# C_3_1.net
KiCad netlist of a schematic drawn in EasyEDA Pro
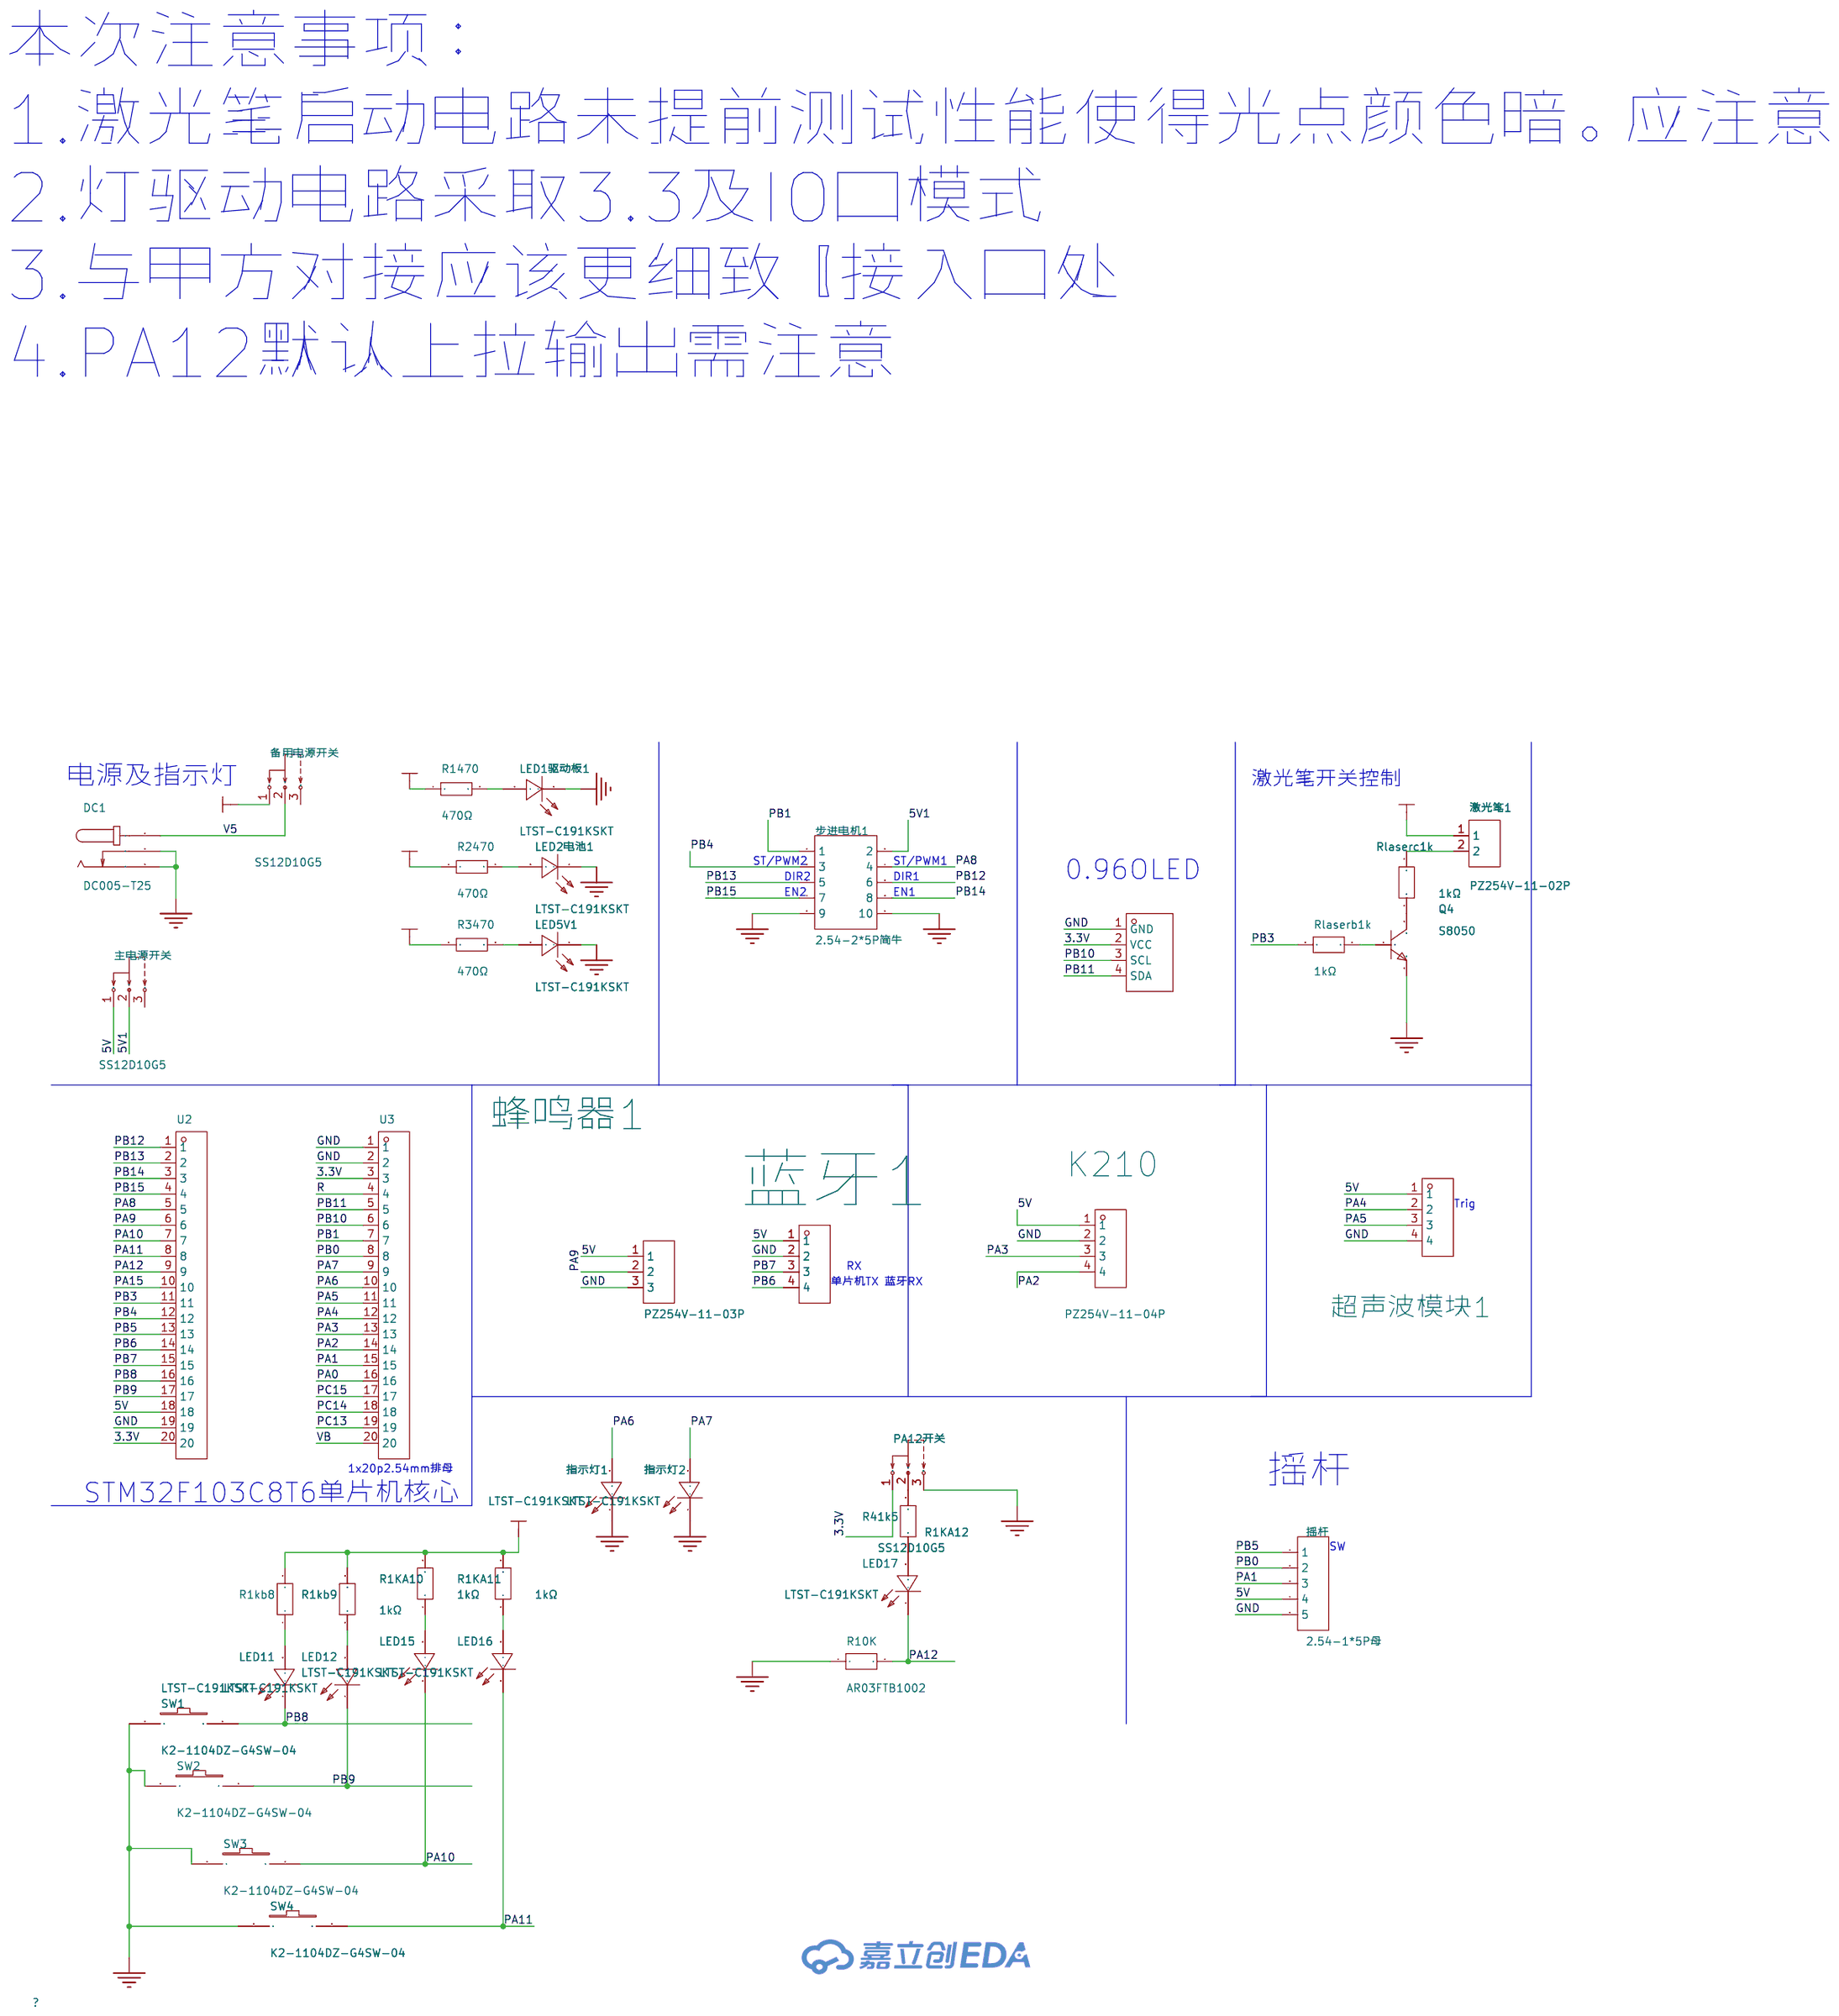
[diagram p0: schematic sheet]

(export (version "E")
  (design (tool "Eeschema 10.0.6"))
  (components
    (comp (ref "DC1")
      (value "DC005-T25")
      (footprint "easyedapro:DC-IN-TH_DC-005-20A-1")
      (description "触点内径:2.5mm;触点外径:6.3mm;额定电流:-;额定电压:-;")
      (fields (field (name "Manufacturer") "SOFNG(硕方)"))
      (libsource (lib "easyedapro") (part "DC005-2.5MM"))
    )
    (comp (ref "K210")
      (value "PZ254V-11-04P")
      (footprint "easyedapro:HDR-TH_4P-P2.54-V-M")
      (fields (field (name "Manufacturer") "XFCN(兴飞)"))
      (libsource (lib "easyedapro") (part "PZ254V-11-04P_C2691448"))
    )
    (comp (ref "LED1驱动板1")
      (value "LTST-C191KSKT")
      (footprint "easyedapro:LED0603-RD-YELLOW")
      (fields (field (name "Manufacturer") "LITEON(光宝)"))
      (libsource (lib "easyedapro") (part "LTST-C191KSKT"))
    )
    (comp (ref "LED2电池1")
      (value "LTST-C191KSKT")
      (footprint "easyedapro:LED0603-RD-YELLOW")
      (fields (field (name "Manufacturer") "LITEON(光宝)"))
      (libsource (lib "easyedapro") (part "LTST-C191KSKT"))
    )
    (comp (ref "LED5V1")
      (value "LTST-C191KSKT")
      (footprint "easyedapro:LED0603-RD-YELLOW")
      (fields (field (name "Manufacturer") "LITEON(光宝)"))
      (libsource (lib "easyedapro") (part "LTST-C191KSKT"))
    )
    (comp (ref "LED11")
      (value "LTST-C191KSKT")
      (footprint "easyedapro:LED0603-RD-YELLOW")
      (fields (field (name "Manufacturer") "LITEON(光宝)"))
      (libsource (lib "easyedapro") (part "LTST-C191KSKT"))
    )
    (comp (ref "LED12")
      (value "LTST-C191KSKT")
      (footprint "easyedapro:LED0603-RD-YELLOW")
      (fields (field (name "Manufacturer") "LITEON(光宝)"))
      (libsource (lib "easyedapro") (part "LTST-C191KSKT"))
    )
    (comp (ref "LED15")
      (value "LTST-C191KSKT")
      (footprint "easyedapro:LED0603-RD-YELLOW")
      (fields (field (name "Manufacturer") "LITEON(光宝)"))
      (libsource (lib "easyedapro") (part "LTST-C191KSKT"))
    )
    (comp (ref "LED16")
      (value "LTST-C191KSKT")
      (footprint "easyedapro:LED0603-RD-YELLOW")
      (fields (field (name "Manufacturer") "LITEON(光宝)"))
      (libsource (lib "easyedapro") (part "LTST-C191KSKT"))
    )
    (comp (ref "LED17")
      (value "LTST-C191KSKT")
      (footprint "easyedapro:LED0603-RD-YELLOW")
      (fields (field (name "Manufacturer") "LITEON(光宝)"))
      (libsource (lib "easyedapro") (part "LTST-C191KSKT"))
    )
    (comp (ref "OLED1")
      (value "HS96L03W2C03")
      (footprint "easyedapro:OLED-TH_L27.8-W27.2-P2.54_C9900033791")
      (description "主控芯片:SSD1315;接口类型:I2C;尺寸(inch):0.96;像素分辨率:128x64;")
      (fields (field (name "Manufacturer") "HS(汉昇)"))
      (libsource (lib "easyedapro") (part "HS96L03W2C03"))
    )
    (comp (ref "PA12开关")
      (value "SS12D10G5")
      (footprint "easyedapro:SW-TH_SHOU-HAN_SS12D10G4")
      (description "电路结构:单刀双掷;安装方式:直插;额定电流(DC):2A;额定电压(DC):125V;机械寿命:3千次;")
      (fields (field (name "Manufacturer") "SHOU HAN(首韩)"))
      (libsource (lib "easyedapro") (part "SS12D10G5"))
    )
    (comp (ref "Q4")
      (value "S8050")
      (footprint "easyedapro:SOT-23-3_L2.9-W1.6-P1.90-LS2.8-BR")
      (description "晶体管类型:NPN;集电极电流(Ic):500mA;集射极击穿电压(Vceo):25V;功率(Pd):300mW;")
      (fields (field (name "Manufacturer") "Hottech(合科泰)"))
      (libsource (lib "easyedapro") (part "S8050_C181158"))
    )
    (comp (ref "R1KA10")
      (value "1kΩ")
      (footprint "easyedapro:R0603")
      (description "电阻类型:厚膜电阻;阻值:1kΩ;精度:±1%;功率:100mW;最大工作电压:75V;")
      (fields (field (name "Manufacturer Part") "FCR0603F1K") (field (name "Manufacturer") "VO(翔胜)"))
      (libsource (lib "easyedapro") (part "FCR0603F1K"))
    )
    (comp (ref "R1KA11")
      (value "1kΩ")
      (footprint "easyedapro:R0603")
      (description "电阻类型:厚膜电阻;阻值:1kΩ;精度:±1%;功率:100mW;最大工作电压:75V;")
      (fields (field (name "Manufacturer Part") "FCR0603F1K") (field (name "Manufacturer") "VO(翔胜)"))
      (libsource (lib "easyedapro") (part "FCR0603F1K"))
    )
    (comp (ref "R1kb8")
      (value "1kΩ")
      (footprint "easyedapro:R0603")
      (description "电阻类型:厚膜电阻;阻值:1kΩ;精度:±1%;功率:100mW;最大工作电压:75V;")
      (fields (field (name "Manufacturer Part") "FCR0603F1K") (field (name "Manufacturer") "VO(翔胜)"))
      (libsource (lib "easyedapro") (part "FCR0603F1K"))
    )
    (comp (ref "R1kb9")
      (value "1kΩ")
      (footprint "easyedapro:R0603")
      (description "电阻类型:厚膜电阻;阻值:1kΩ;精度:±1%;功率:100mW;最大工作电压:75V;")
      (fields (field (name "Manufacturer Part") "FCR0603F1K") (field (name "Manufacturer") "VO(翔胜)"))
      (libsource (lib "easyedapro") (part "FCR0603F1K"))
    )
    (comp (ref "R10K")
      (value "AR03FTB1002")
      (footprint "easyedapro:R0603")
      (fields (field (name "Manufacturer") "Viking(光颉)"))
      (libsource (lib "easyedapro") (part "AR03FTB1002"))
    )
    (comp (ref "R41k5")
      (value "1kΩ")
      (footprint "easyedapro:R0603")
      (description "电阻类型:厚膜电阻;阻值:1kΩ;精度:±1%;功率:100mW;最大工作电压:75V;")
      (fields (field (name "Manufacturer Part") "FCR0603F1K") (field (name "Manufacturer") "VO(翔胜)"))
      (libsource (lib "easyedapro") (part "FCR0603F1K"))
    )
    (comp (ref "R1470")
      (value "470Ω")
      (footprint "easyedapro:R0603")
      (description "电阻类型:厚膜电阻;阻值:470Ω;精度:±1%;功率:100mW;最大工作电压:75V;温度系数:±100ppm/°C;")
      (fields
        (field (name "Manufacturer Part") "0603WAF4700T5E")
        (field (name "Manufacturer") "UNI-ROYAL(厚声)")
      )
      (libsource (lib "easyedapro") (part "0603WAF4700T5E"))
    )
    (comp (ref "R2470")
      (value "470Ω")
      (footprint "easyedapro:R0603")
      (description "电阻类型:厚膜电阻;阻值:470Ω;精度:±1%;功率:100mW;最大工作电压:75V;温度系数:±100ppm/°C;")
      (fields
        (field (name "Manufacturer Part") "0603WAF4700T5E")
        (field (name "Manufacturer") "UNI-ROYAL(厚声)")
      )
      (libsource (lib "easyedapro") (part "0603WAF4700T5E"))
    )
    (comp (ref "R3470")
      (value "470Ω")
      (footprint "easyedapro:R0603")
      (description "电阻类型:厚膜电阻;阻值:470Ω;精度:±1%;功率:100mW;最大工作电压:75V;温度系数:±100ppm/°C;")
      (fields
        (field (name "Manufacturer Part") "0603WAF4700T5E")
        (field (name "Manufacturer") "UNI-ROYAL(厚声)")
      )
      (libsource (lib "easyedapro") (part "0603WAF4700T5E"))
    )
    (comp (ref "Rlaserb1k")
      (value "1kΩ")
      (footprint "easyedapro:R0603")
      (description "电阻类型:厚膜电阻;阻值:1kΩ;精度:±1%;功率:100mW;最大工作电压:75V;")
      (fields (field (name "Manufacturer Part") "FCR0603F1K") (field (name "Manufacturer") "VO(翔胜)"))
      (libsource (lib "easyedapro") (part "FCR0603F1K"))
    )
    (comp (ref "Rlaserc1k")
      (value "1kΩ")
      (footprint "easyedapro:R0603")
      (description "电阻类型:厚膜电阻;阻值:1kΩ;精度:±1%;功率:100mW;最大工作电压:75V;")
      (fields (field (name "Manufacturer Part") "FCR0603F1K") (field (name "Manufacturer") "VO(翔胜)"))
      (libsource (lib "easyedapro") (part "FCR0603F1K"))
    )
    (comp (ref "SW1")
      (value "K2-1104DZ-G4SW-04")
      (footprint "easyedapro:KEY-TH_2P-L6.0-W6.0-P5.00")
      (description "作用力:250gf;安装方式:直插;开关长度:6mm;开关宽度:6mm;开关高度:7mm;触点电流:50mA;额定电压(DC):12V;绝缘电阻:100MΩ;机械寿命:10万次;")
      (fields (field (name "Manufacturer") "韩国韩荣"))
      (libsource (lib "easyedapro") (part "K2-1104DZ-G4SW-04"))
    )
    (comp (ref "SW2")
      (value "K2-1104DZ-G4SW-04")
      (footprint "easyedapro:KEY-TH_2P-L6.0-W6.0-P5.00")
      (description "作用力:250gf;安装方式:直插;开关长度:6mm;开关宽度:6mm;开关高度:7mm;触点电流:50mA;额定电压(DC):12V;绝缘电阻:100MΩ;机械寿命:10万次;")
      (fields (field (name "Manufacturer") "韩国韩荣"))
      (libsource (lib "easyedapro") (part "K2-1104DZ-G4SW-04"))
    )
    (comp (ref "SW3")
      (value "K2-1104DZ-G4SW-04")
      (footprint "easyedapro:KEY-TH_2P-L6.0-W6.0-P5.00")
      (description "作用力:250gf;安装方式:直插;开关长度:6mm;开关宽度:6mm;开关高度:7mm;触点电流:50mA;额定电压(DC):12V;绝缘电阻:100MΩ;机械寿命:10万次;")
      (fields (field (name "Manufacturer") "韩国韩荣"))
      (libsource (lib "easyedapro") (part "K2-1104DZ-G4SW-04"))
    )
    (comp (ref "SW4")
      (value "K2-1104DZ-G4SW-04")
      (footprint "easyedapro:KEY-TH_2P-L6.0-W6.0-P5.00")
      (description "作用力:250gf;安装方式:直插;开关长度:6mm;开关宽度:6mm;开关高度:7mm;触点电流:50mA;额定电压(DC):12V;绝缘电阻:100MΩ;机械寿命:10万次;")
      (fields (field (name "Manufacturer") "韩国韩荣"))
      (libsource (lib "easyedapro") (part "K2-1104DZ-G4SW-04"))
    )
    (comp (ref "U2")
      (value "KH-2FH-1X20P-H4.3")
      (footprint "easyedapro:HDR-TH_20P-P2.00-V-F-A")
      (fields (field (name "Manufacturer") "kinghelm(金航标)"))
      (libsource (lib "easyedapro") (part "KH-2FH-1X20P-H4.3"))
    )
    (comp (ref "U3")
      (value "KH-2FH-1X20P-H4.3")
      (footprint "easyedapro:HDR-TH_20P-P2.00-V-F-A")
      (fields (field (name "Manufacturer") "kinghelm(金航标)"))
      (libsource (lib "easyedapro") (part "KH-2FH-1X20P-H4.3"))
    )
    (comp (ref "主电源开关")
      (value "SS12D10G5")
      (footprint "easyedapro:SW-TH_SHOU-HAN_SS12D10G4")
      (description "电路结构:单刀双掷;安装方式:直插;额定电流(DC):2A;额定电压(DC):125V;机械寿命:3千次;")
      (fields (field (name "Manufacturer") "SHOU HAN(首韩)"))
      (libsource (lib "easyedapro") (part "SS12D10G5"))
    )
    (comp (ref "备用电源开关")
      (value "SS12D10G5")
      (footprint "easyedapro:SW-TH_SHOU-HAN_SS12D10G4")
      (description "电路结构:单刀双掷;安装方式:直插;额定电流(DC):2A;额定电压(DC):125V;机械寿命:3千次;")
      (fields (field (name "Manufacturer") "SHOU HAN(首韩)"))
      (libsource (lib "easyedapro") (part "SS12D10G5"))
    )
    (comp (ref "指示灯1")
      (value "LTST-C191KSKT")
      (footprint "easyedapro:LED0603-RD-YELLOW")
      (fields (field (name "Manufacturer") "LITEON(光宝)"))
      (libsource (lib "easyedapro") (part "LTST-C191KSKT"))
    )
    (comp (ref "指示灯2")
      (value "LTST-C191KSKT")
      (footprint "easyedapro:LED0603-RD-YELLOW")
      (fields (field (name "Manufacturer") "LITEON(光宝)"))
      (libsource (lib "easyedapro") (part "LTST-C191KSKT"))
    )
    (comp (ref "摇杆")
      (value "2.54-1*5P母")
      (footprint "easyedapro:HDR-TH_5P-P2.54-V-F")
      (description "插孔结构:1x5P;间距:2.54mm;行距:-;安装类型:直插;排数:单排;总孔位数:5P;塑高:-;触头材质:-;触头镀层:-;")
      (fields (field (name "Manufacturer") "BOOMELE(博穆精密)"))
      (libsource (lib "easyedapro") (part "Header-Female-2.54_1x5"))
    )
    (comp (ref "步进电机1")
      (value "2.54-2*5P简牛")
      (footprint "easyedapro:IDC-TH_10P-P2.54_C5665")
      (description "连接器类型:简牛座;间距:2.54mm;结构:2x5P;封装形式:直插;行距:2.54mm;排数:2;每排PIN数:5;触头材质:-;触头镀层:-;")
      (fields (field (name "Manufacturer") "BOOMELE(博穆精密)"))
      (libsource (lib "easyedapro") (part "HDR-IDC-2.54-2X5P"))
    )
    (comp (ref "激光笔1")
      (value "PZ254V-11-02P")
      (footprint "easyedapro:HDR-TH_2P-P2.54-V-M")
      (fields (field (name "Manufacturer") "XFCN(兴飞)"))
      (libsource (lib "easyedapro") (part "PZ254V-11-02P"))
    )
    (comp (ref "蓝牙1")
      (value "2.54-1*4P母")
      (footprint "easyedapro:HDR-TH_4P-P2.54-V-F")
      (fields (field (name "Manufacturer") "BOOMELE(博穆精密)"))
      (libsource (lib "easyedapro") (part "2.54-1*4P母"))
    )
    (comp (ref "蜂鸣器1")
      (value "PZ254V-11-03P")
      (footprint "easyedapro:HDR-TH_3P-P2.54-V-M")
      (fields (field (name "Manufacturer") "XFCN(兴飞)"))
      (libsource (lib "easyedapro") (part "PZ254V-11-03P_C2937625"))
    )
    (comp (ref "超声波模块1")
      (value "KH-2.54FH-1X4P-H8.5")
      (footprint "easyedapro:HDR-TH_4P-P2.54-V-F")
      (fields (field (name "Manufacturer") "kinghelm(金航标)"))
      (libsource (lib "easyedapro") (part "KH-2.54FH-1X4P-H8.5"))
    )
  )
  (nets
    (net (code "1") (name "/PA0") (class "Default")
      (node (ref "U3") (pin "16") (pinfunction "16_16") (pintype "unspecified"))
    )
    (net (code "2") (name "/PA1") (class "Default")
      (node (ref "U3") (pin "15") (pinfunction "15_15") (pintype "unspecified"))
      (node (ref "摇杆") (pin "3") (pinfunction "3_3") (pintype "input"))
    )
    (net (code "3") (name "/PA2") (class "Default")
      (node (ref "K210") (pin "4") (pinfunction "4_4") (pintype "unspecified"))
      (node (ref "U3") (pin "14") (pinfunction "14_14") (pintype "unspecified"))
    )
    (net (code "4") (name "/PA3") (class "Default")
      (node (ref "K210") (pin "3") (pinfunction "3_3") (pintype "unspecified"))
      (node (ref "U3") (pin "13") (pinfunction "13_13") (pintype "unspecified"))
    )
    (net (code "5") (name "/PA4") (class "Default")
      (node (ref "U3") (pin "12") (pinfunction "12_12") (pintype "unspecified"))
      (node (ref "超声波模块1") (pin "2") (pinfunction "2_2") (pintype "unspecified"))
    )
    (net (code "6") (name "/PA5") (class "Default")
      (node (ref "U3") (pin "11") (pinfunction "11_11") (pintype "unspecified"))
      (node (ref "超声波模块1") (pin "3") (pinfunction "3_3") (pintype "unspecified"))
    )
    (net (code "7") (name "/PA6") (class "Default")
      (node (ref "U3") (pin "10") (pinfunction "10_10") (pintype "unspecified"))
      (node (ref "指示灯1") (pin "2") (pinfunction "+_2") (pintype "unspecified"))
    )
    (net (code "8") (name "/PA7") (class "Default")
      (node (ref "U3") (pin "9") (pinfunction "9_9") (pintype "unspecified"))
      (node (ref "指示灯2") (pin "2") (pinfunction "+_2") (pintype "unspecified"))
    )
    (net (code "9") (name "/PA8") (class "Default")
      (node (ref "U2") (pin "5") (pinfunction "5_5") (pintype "unspecified"))
      (node (ref "步进电机1") (pin "4") (pinfunction "4_4") (pintype "unspecified"))
    )
    (net (code "10") (name "/PA9") (class "Default")
      (node (ref "U2") (pin "6") (pinfunction "6_6") (pintype "unspecified"))
      (node (ref "蜂鸣器1") (pin "2") (pinfunction "2_2") (pintype "unspecified"))
    )
    (net (code "11") (name "/PA10") (class "Default")
      (node (ref "LED15") (pin "1") (pinfunction "-_1") (pintype "unspecified"))
      (node (ref "SW3") (pin "2") (pinfunction "2_2") (pintype "input"))
      (node (ref "U2") (pin "7") (pinfunction "7_7") (pintype "unspecified"))
    )
    (net (code "12") (name "/PA11") (class "Default")
      (node (ref "LED16") (pin "1") (pinfunction "-_1") (pintype "unspecified"))
      (node (ref "SW4") (pin "2") (pinfunction "2_2") (pintype "input"))
      (node (ref "U2") (pin "8") (pinfunction "8_8") (pintype "unspecified"))
    )
    (net (code "13") (name "/PA12") (class "Default")
      (node (ref "LED17") (pin "1") (pinfunction "-_1") (pintype "unspecified"))
      (node (ref "R10K") (pin "2") (pinfunction "2_2") (pintype "unspecified"))
      (node (ref "U2") (pin "9") (pinfunction "9_9") (pintype "unspecified"))
    )
    (net (code "14") (name "/PA15") (class "Default")
      (node (ref "U2") (pin "10") (pinfunction "10_10") (pintype "unspecified"))
    )
    (net (code "15") (name "/PB0") (class "Default")
      (node (ref "U3") (pin "8") (pinfunction "8_8") (pintype "unspecified"))
      (node (ref "摇杆") (pin "2") (pinfunction "2_2") (pintype "input"))
    )
    (net (code "16") (name "/PB1") (class "Default")
      (node (ref "U3") (pin "7") (pinfunction "7_7") (pintype "unspecified"))
      (node (ref "步进电机1") (pin "1") (pinfunction "1_1") (pintype "unspecified"))
    )
    (net (code "17") (name "/PB3") (class "Default")
      (node (ref "Rlaserb1k") (pin "2") (pinfunction "2_2") (pintype "unspecified"))
      (node (ref "U2") (pin "11") (pinfunction "11_11") (pintype "unspecified"))
    )
    (net (code "18") (name "/PB4") (class "Default")
      (node (ref "U2") (pin "12") (pinfunction "12_12") (pintype "unspecified"))
      (node (ref "步进电机1") (pin "3") (pinfunction "3_3") (pintype "unspecified"))
    )
    (net (code "19") (name "/PB5") (class "Default")
      (node (ref "U2") (pin "13") (pinfunction "13_13") (pintype "unspecified"))
      (node (ref "摇杆") (pin "1") (pinfunction "1_1") (pintype "input"))
    )
    (net (code "20") (name "/PB6") (class "Default")
      (node (ref "U2") (pin "14") (pinfunction "14_14") (pintype "unspecified"))
      (node (ref "蓝牙1") (pin "4") (pinfunction "4_4") (pintype "unspecified"))
    )
    (net (code "21") (name "/PB7") (class "Default")
      (node (ref "U2") (pin "15") (pinfunction "15_15") (pintype "unspecified"))
      (node (ref "蓝牙1") (pin "3") (pinfunction "3_3") (pintype "unspecified"))
    )
    (net (code "22") (name "/PB8") (class "Default")
      (node (ref "LED11") (pin "1") (pinfunction "-_1") (pintype "unspecified"))
      (node (ref "SW1") (pin "2") (pinfunction "2_2") (pintype "input"))
      (node (ref "U2") (pin "16") (pinfunction "16_16") (pintype "unspecified"))
    )
    (net (code "23") (name "/PB9") (class "Default")
      (node (ref "LED12") (pin "1") (pinfunction "-_1") (pintype "unspecified"))
      (node (ref "SW2") (pin "2") (pinfunction "2_2") (pintype "input"))
      (node (ref "U2") (pin "17") (pinfunction "17_17") (pintype "unspecified"))
    )
    (net (code "24") (name "/PB10") (class "Default")
      (node (ref "OLED1") (pin "3") (pinfunction "SCL_3") (pintype "unspecified"))
      (node (ref "U3") (pin "6") (pinfunction "6_6") (pintype "unspecified"))
    )
    (net (code "25") (name "/PB11") (class "Default")
      (node (ref "OLED1") (pin "4") (pinfunction "SDA_4") (pintype "unspecified"))
      (node (ref "U3") (pin "5") (pinfunction "5_5") (pintype "unspecified"))
    )
    (net (code "26") (name "/PB12") (class "Default")
      (node (ref "U2") (pin "1") (pinfunction "1_1") (pintype "unspecified"))
      (node (ref "步进电机1") (pin "6") (pinfunction "6_6") (pintype "unspecified"))
    )
    (net (code "27") (name "/PB13") (class "Default")
      (node (ref "U2") (pin "2") (pinfunction "2_2") (pintype "unspecified"))
      (node (ref "步进电机1") (pin "5") (pinfunction "5_5") (pintype "unspecified"))
    )
    (net (code "28") (name "/PB14") (class "Default")
      (node (ref "U2") (pin "3") (pinfunction "3_3") (pintype "unspecified"))
      (node (ref "步进电机1") (pin "8") (pinfunction "8_8") (pintype "unspecified"))
    )
    (net (code "29") (name "/PB15") (class "Default")
      (node (ref "U2") (pin "4") (pinfunction "4_4") (pintype "unspecified"))
      (node (ref "步进电机1") (pin "7") (pinfunction "7_7") (pintype "unspecified"))
    )
    (net (code "30") (name "/PC13") (class "Default")
      (node (ref "U3") (pin "19") (pinfunction "19_19") (pintype "unspecified"))
    )
    (net (code "31") (name "/PC14") (class "Default")
      (node (ref "U3") (pin "18") (pinfunction "18_18") (pintype "unspecified"))
    )
    (net (code "32") (name "/PC15") (class "Default")
      (node (ref "U3") (pin "17") (pinfunction "17_17") (pintype "unspecified"))
    )
    (net (code "33") (name "/R") (class "Default")
      (node (ref "U3") (pin "4") (pinfunction "4_4") (pintype "unspecified"))
    )
    (net (code "34") (name "/VB") (class "Default")
      (node (ref "U3") (pin "20") (pinfunction "20_20") (pintype "unspecified"))
    )
    (net (code "35") (name "3.3V") (class "Default")
      (node (ref "OLED1") (pin "2") (pinfunction "VCC_2") (pintype "unspecified"))
      (node (ref "PA12开关") (pin "1") (pinfunction "1_1") (pintype "unspecified"))
      (node (ref "R1KA10") (pin "2") (pinfunction "2_2") (pintype "unspecified"))
      (node (ref "R1KA11") (pin "2") (pinfunction "2_2") (pintype "unspecified"))
      (node (ref "R1kb8") (pin "2") (pinfunction "2_2") (pintype "unspecified"))
      (node (ref "R1kb9") (pin "2") (pinfunction "2_2") (pintype "unspecified"))
      (node (ref "U2") (pin "20") (pinfunction "20_20") (pintype "unspecified"))
      (node (ref "U3") (pin "3") (pinfunction "3_3") (pintype "unspecified"))
    )
    (net (code "36") (name "5V") (class "Default")
      (node (ref "K210") (pin "1") (pinfunction "1_1") (pintype "unspecified"))
      (node (ref "R3470") (pin "1") (pinfunction "1_1") (pintype "input"))
      (node (ref "U2") (pin "18") (pinfunction "18_18") (pintype "unspecified"))
      (node (ref "主电源开关") (pin "1") (pinfunction "1_1") (pintype "unspecified"))
      (node (ref "备用电源开关") (pin "1") (pinfunction "1_1") (pintype "unspecified"))
      (node (ref "摇杆") (pin "4") (pinfunction "4_4") (pintype "input"))
      (node (ref "激光笔1") (pin "1") (pinfunction "1_1") (pintype "unspecified"))
      (node (ref "蓝牙1") (pin "1") (pinfunction "1_1") (pintype "unspecified"))
      (node (ref "蜂鸣器1") (pin "1") (pinfunction "1_1") (pintype "unspecified"))
      (node (ref "超声波模块1") (pin "1") (pinfunction "1_1") (pintype "unspecified"))
    )
    (net (code "37") (name "5V1") (class "Default")
      (node (ref "R1470") (pin "1") (pinfunction "1_1") (pintype "input"))
      (node (ref "主电源开关") (pin "2") (pinfunction "2_2") (pintype "unspecified"))
      (node (ref "步进电机1") (pin "2") (pinfunction "2_2") (pintype "unspecified"))
    )
    (net (code "38") (name "GND") (class "Default")
      (node (ref "DC1") (pin "2") (pinfunction "2_2") (pintype "unspecified"))
      (node (ref "DC1") (pin "3") (pinfunction "3_3") (pintype "unspecified"))
      (node (ref "K210") (pin "2") (pinfunction "2_2") (pintype "unspecified"))
      (node (ref "LED1驱动板1") (pin "1") (pinfunction "-_1") (pintype "unspecified"))
      (node (ref "LED2电池1") (pin "1") (pinfunction "-_1") (pintype "unspecified"))
      (node (ref "LED5V1") (pin "1") (pinfunction "-_1") (pintype "unspecified"))
      (node (ref "OLED1") (pin "1") (pinfunction "GND_1") (pintype "unspecified"))
      (node (ref "PA12开关") (pin "3") (pinfunction "3_3") (pintype "unspecified"))
      (node (ref "Q4") (pin "2") (pinfunction "2_2") (pintype "input"))
      (node (ref "R10K") (pin "1") (pinfunction "1_1") (pintype "unspecified"))
      (node (ref "SW1") (pin "1") (pinfunction "1_1") (pintype "input"))
      (node (ref "SW2") (pin "1") (pinfunction "1_1") (pintype "input"))
      (node (ref "SW3") (pin "1") (pinfunction "1_1") (pintype "input"))
      (node (ref "SW4") (pin "1") (pinfunction "1_1") (pintype "input"))
      (node (ref "U2") (pin "19") (pinfunction "19_19") (pintype "unspecified"))
      (node (ref "U3") (pin "1") (pinfunction "1_1") (pintype "unspecified"))
      (node (ref "U3") (pin "2") (pinfunction "2_2") (pintype "unspecified"))
      (node (ref "指示灯1") (pin "1") (pinfunction "-_1") (pintype "unspecified"))
      (node (ref "指示灯2") (pin "1") (pinfunction "-_1") (pintype "unspecified"))
      (node (ref "摇杆") (pin "5") (pinfunction "5_5") (pintype "input"))
      (node (ref "步进电机1") (pin "10") (pinfunction "10_10") (pintype "unspecified"))
      (node (ref "步进电机1") (pin "9") (pinfunction "9_9") (pintype "unspecified"))
      (node (ref "蓝牙1") (pin "2") (pinfunction "2_2") (pintype "unspecified"))
      (node (ref "蜂鸣器1") (pin "3") (pinfunction "3_3") (pintype "unspecified"))
      (node (ref "超声波模块1") (pin "4") (pinfunction "4_4") (pintype "unspecified"))
    )
    (net (code "39") (name "Net-(LED1驱动板1-+)") (class "Default")
      (node (ref "LED1驱动板1") (pin "2") (pinfunction "+_2") (pintype "unspecified"))
      (node (ref "R1470") (pin "2") (pinfunction "2_2") (pintype "input"))
    )
    (net (code "40") (name "Net-(LED2电池1-+)") (class "Default")
      (node (ref "LED2电池1") (pin "2") (pinfunction "+_2") (pintype "unspecified"))
      (node (ref "R2470") (pin "2") (pinfunction "2_2") (pintype "input"))
    )
    (net (code "41") (name "Net-(LED5V1-+)") (class "Default")
      (node (ref "LED5V1") (pin "2") (pinfunction "+_2") (pintype "unspecified"))
      (node (ref "R3470") (pin "2") (pinfunction "2_2") (pintype "input"))
    )
    (net (code "42") (name "Net-(LED11-+)") (class "Default")
      (node (ref "LED11") (pin "2") (pinfunction "+_2") (pintype "unspecified"))
      (node (ref "R1kb8") (pin "1") (pinfunction "1_1") (pintype "unspecified"))
    )
    (net (code "43") (name "Net-(LED12-+)") (class "Default")
      (node (ref "LED12") (pin "2") (pinfunction "+_2") (pintype "unspecified"))
      (node (ref "R1kb9") (pin "1") (pinfunction "1_1") (pintype "unspecified"))
    )
    (net (code "44") (name "Net-(LED15-+)") (class "Default")
      (node (ref "LED15") (pin "2") (pinfunction "+_2") (pintype "unspecified"))
      (node (ref "R1KA10") (pin "1") (pinfunction "1_1") (pintype "unspecified"))
    )
    (net (code "45") (name "Net-(LED16-+)") (class "Default")
      (node (ref "LED16") (pin "2") (pinfunction "+_2") (pintype "unspecified"))
      (node (ref "R1KA11") (pin "1") (pinfunction "1_1") (pintype "unspecified"))
    )
    (net (code "46") (name "Net-(LED17-+)") (class "Default")
      (node (ref "LED17") (pin "2") (pinfunction "+_2") (pintype "unspecified"))
      (node (ref "R41k5") (pin "1") (pinfunction "1_1") (pintype "unspecified"))
    )
    (net (code "47") (name "Net-(PA12开关-Pad2)") (class "Default")
      (node (ref "PA12开关") (pin "2") (pinfunction "2_2") (pintype "unspecified"))
      (node (ref "R41k5") (pin "2") (pinfunction "2_2") (pintype "unspecified"))
    )
    (net (code "48") (name "Net-(Q4-Pad1)") (class "Default")
      (node (ref "Q4") (pin "1") (pinfunction "1_1") (pintype "input"))
      (node (ref "Rlaserb1k") (pin "1") (pinfunction "1_1") (pintype "unspecified"))
    )
    (net (code "49") (name "Net-(Q4-Pad3)") (class "Default")
      (node (ref "Q4") (pin "3") (pinfunction "3_3") (pintype "input"))
      (node (ref "Rlaserc1k") (pin "1") (pinfunction "1_1") (pintype "unspecified"))
    )
    (net (code "50") (name "Net-(Rlaserc1k-Pad2)") (class "Default")
      (node (ref "Rlaserc1k") (pin "2") (pinfunction "2_2") (pintype "unspecified"))
      (node (ref "激光笔1") (pin "2") (pinfunction "2_2") (pintype "unspecified"))
    )
    (net (code "51") (name "V5") (class "Default")
      (node (ref "DC1") (pin "1") (pinfunction "1_1") (pintype "unspecified"))
      (node (ref "R2470") (pin "1") (pinfunction "1_1") (pintype "input"))
      (node (ref "备用电源开关") (pin "2") (pinfunction "2_2") (pintype "unspecified"))
    )
    (net (code "52") (name "unconnected-(主电源开关-Pad3)") (class "Default")
      (node (ref "主电源开关") (pin "3") (pinfunction "3_3") (pintype "unspecified"))
    )
    (net (code "53") (name "unconnected-(备用电源开关-Pad3)") (class "Default")
      (node (ref "备用电源开关") (pin "3") (pinfunction "3_3") (pintype "unspecified"))
    )
  )
)
